# 222.net
KiCad netlist of a schematic drawn in Altium Designer
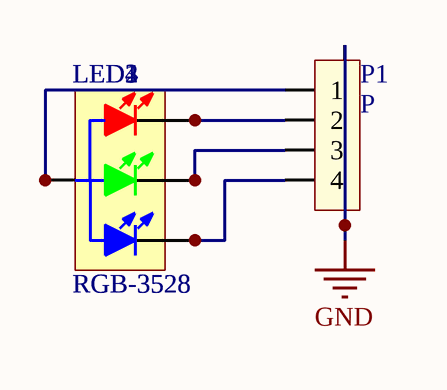
[diagram p0: 222.SchDoc]

(export (version "E")
  (design (tool "Eeschema 10.0.6"))
  (components
    (comp (ref "LED1")
      (value "RGB-3528")
      (footprint "LED 3528-4Pin")
      (description "三基色LED")
      (libsource (lib "9.1   - LED") (part "LED-RGB-3528"))
    )
    (comp (ref "LED2")
      (value "RGB-3528")
      (footprint "LED 3528-4Pin")
      (description "三基色LED")
      (libsource (lib "9.1   - LED") (part "LED-RGB-3528"))
    )
    (comp (ref "LED3")
      (value "RGB-3528")
      (footprint "LED 3528-4Pin")
      (description "三基色LED")
      (libsource (lib "9.1   - LED") (part "LED-RGB-3528"))
    )
    (comp (ref "LED4")
      (value "RGB-3528")
      (footprint "LED 3528-4Pin")
      (description "三基色LED")
      (libsource (lib "9.1   - LED") (part "LED-RGB-3528"))
    )
    (comp (ref "P1") (value "P") (footprint "SH1.0_4pin") (libsource (lib "0") (part "SH1.0-4")))
  )
  (nets
    (net (code "1") (name "GND") (class "Default")
      (node (ref "P1") (pin "0") (pinfunction "0_0") (pintype "passive"))
    )
    (net (code "2") (name "Net-(LED1-A)") (class "Default")
      (node (ref "LED1") (pin "4") (pinfunction "A_4") (pintype "passive"))
      (node (ref "LED2") (pin "4") (pinfunction "A_4") (pintype "passive"))
      (node (ref "LED3") (pin "4") (pinfunction "A_4") (pintype "passive"))
      (node (ref "LED4") (pin "4") (pinfunction "A_4") (pintype "passive"))
      (node (ref "P1") (pin "1") (pinfunction "1_1") (pintype "passive"))
    )
    (net (code "3") (name "Net-(LED1-BULE_K)") (class "Default")
      (node (ref "LED1") (pin "3") (pinfunction "BULE_K_3") (pintype "passive"))
      (node (ref "LED2") (pin "3") (pinfunction "BULE_K_3") (pintype "passive"))
      (node (ref "LED3") (pin "3") (pinfunction "BULE_K_3") (pintype "passive"))
      (node (ref "LED4") (pin "3") (pinfunction "BULE_K_3") (pintype "passive"))
      (node (ref "P1") (pin "4") (pinfunction "4_4") (pintype "passive"))
    )
    (net (code "4") (name "Net-(LED1-GREEN_K)") (class "Default")
      (node (ref "LED1") (pin "2") (pinfunction "GREEN_K_2") (pintype "passive"))
      (node (ref "LED2") (pin "2") (pinfunction "GREEN_K_2") (pintype "passive"))
      (node (ref "LED3") (pin "2") (pinfunction "GREEN_K_2") (pintype "passive"))
      (node (ref "LED4") (pin "2") (pinfunction "GREEN_K_2") (pintype "passive"))
      (node (ref "P1") (pin "3") (pinfunction "3_3") (pintype "passive"))
    )
    (net (code "5") (name "Net-(LED1-RED_K)") (class "Default")
      (node (ref "LED1") (pin "1") (pinfunction "RED_K_1") (pintype "passive"))
      (node (ref "LED2") (pin "1") (pinfunction "RED_K_1") (pintype "passive"))
      (node (ref "LED3") (pin "1") (pinfunction "RED_K_1") (pintype "passive"))
      (node (ref "LED4") (pin "1") (pinfunction "RED_K_1") (pintype "passive"))
      (node (ref "P1") (pin "2") (pinfunction "2_2") (pintype "passive"))
    )
  )
)
